# mc_board_with_leds.net
KiCad netlist of a schematic drawn in EAGLE
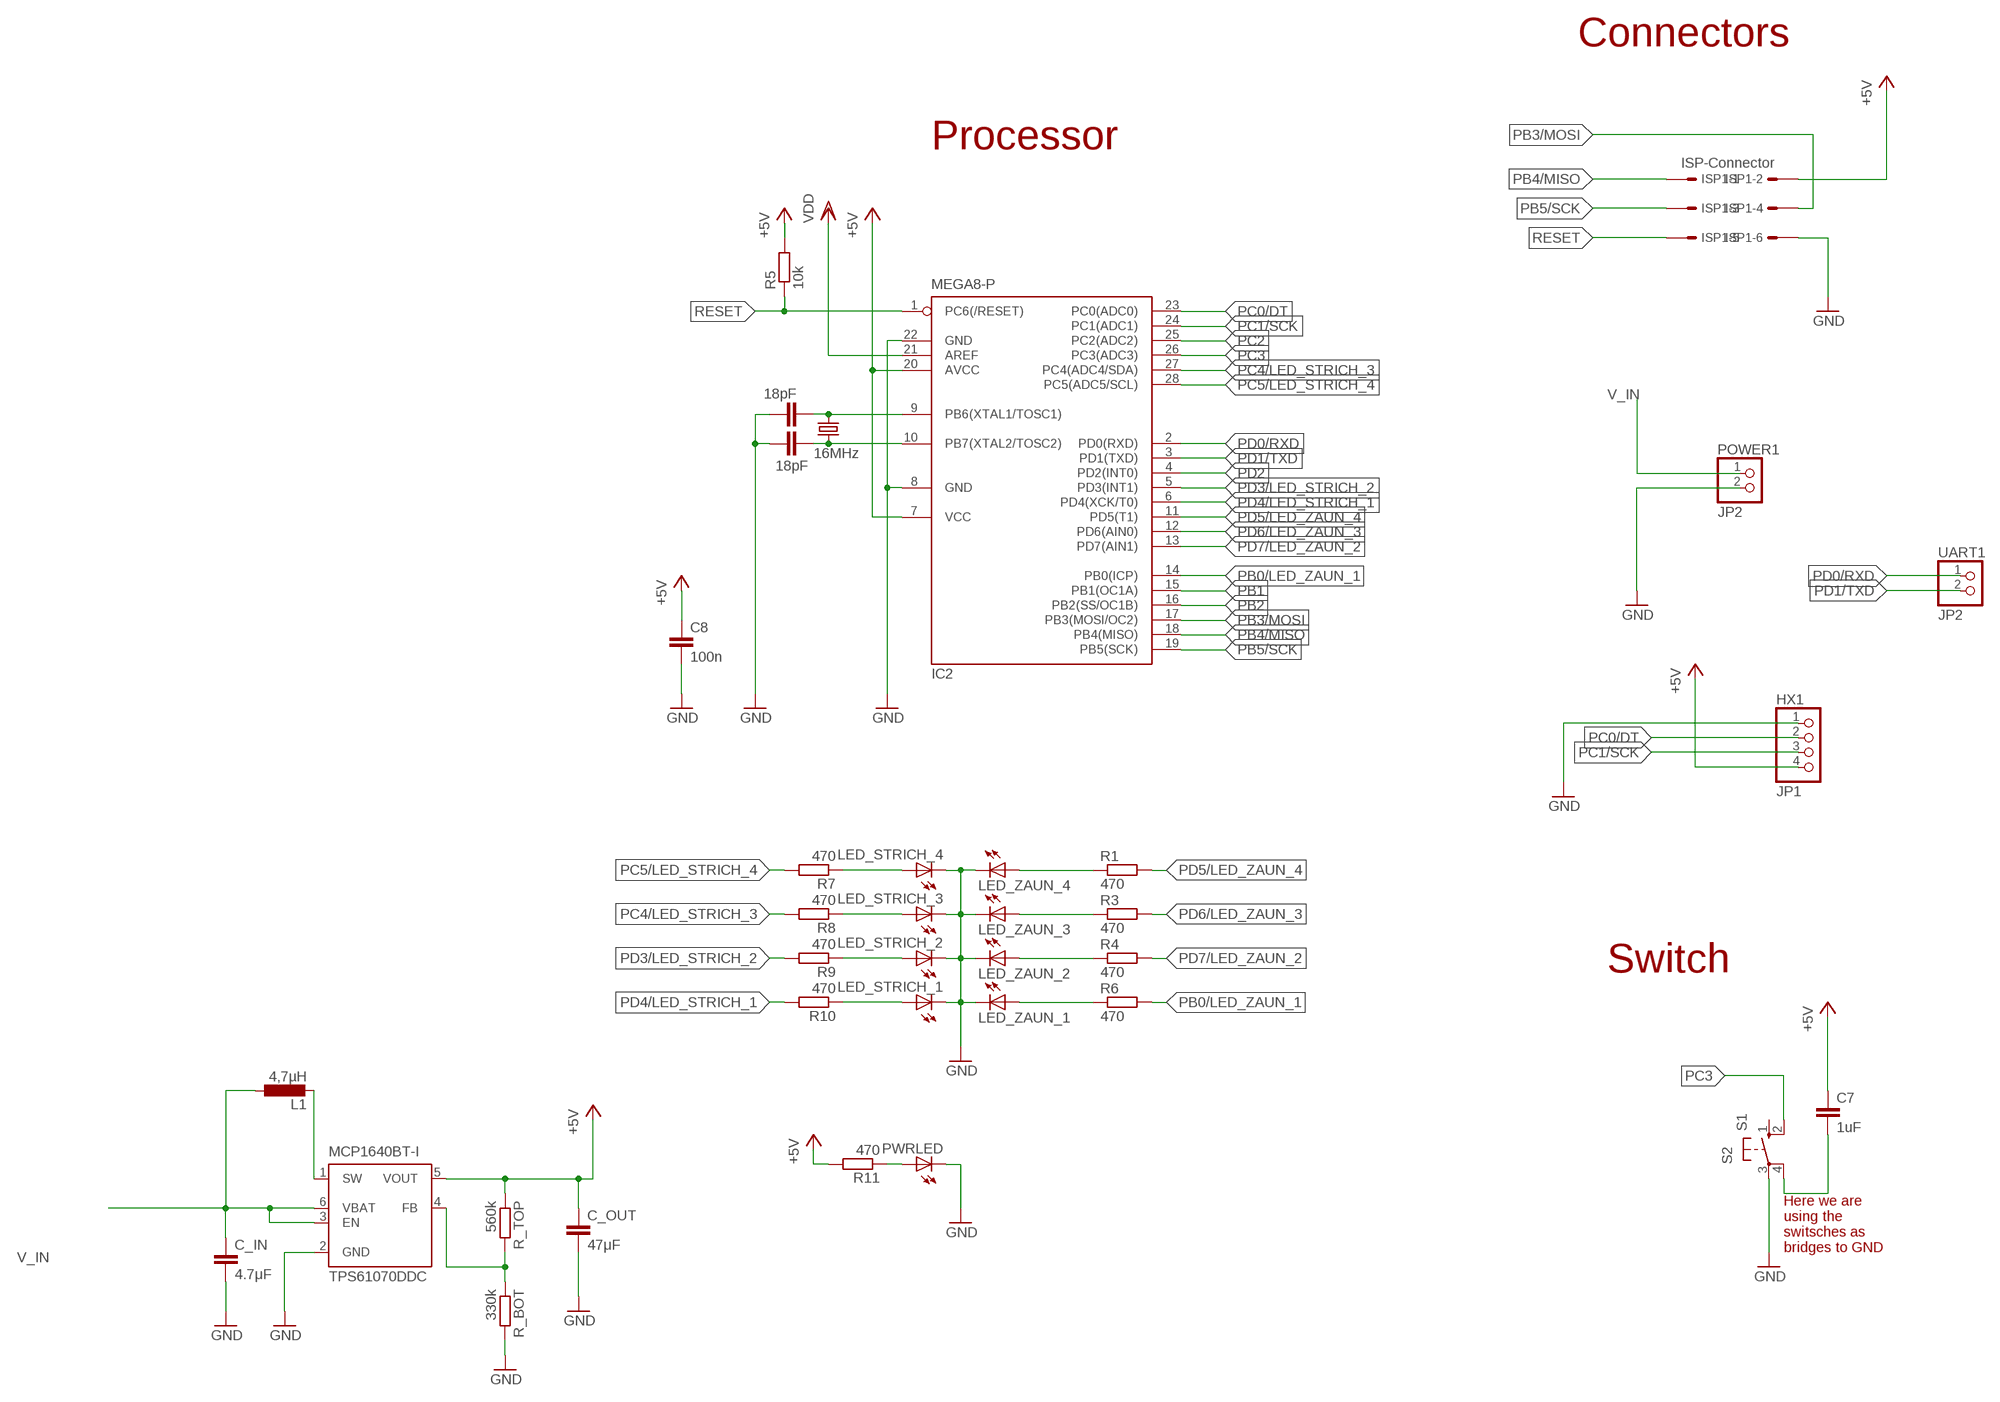
[diagram p0: schematic, sheet 1]

(export (version "E")
  (design (tool "Eeschema 10.0.6"))
  (components
    (comp (ref "C5")
      (value "18pF")
      (footprint "eagle-import:C0805K")
      (libsource (lib "eagle-import") (part "resistor_C-EUC0805K"))
    )
    (comp (ref "C6")
      (value "18pF")
      (footprint "eagle-import:C0805K")
      (libsource (lib "eagle-import") (part "resistor_C-EUC0805K"))
    )
    (comp (ref "C7")
      (value "1uF")
      (footprint "eagle-import:C0805")
      (libsource (lib "eagle-import") (part "C-EUC0805"))
    )
    (comp (ref "C8")
      (value "100n")
      (footprint "eagle-import:C0805")
      (libsource (lib "eagle-import") (part "C-EUC0805"))
    )
    (comp (ref "C_IN")
      (value "4.7μF")
      (footprint "eagle-import:C0805")
      (libsource (lib "eagle-import") (part "C-EUC0805"))
    )
    (comp (ref "C_OUT")
      (value "47μF")
      (footprint "eagle-import:C0805")
      (libsource (lib "eagle-import") (part "C-EUC0805"))
    )
    (comp (ref "HX1")
      (value "JP1")
      (footprint "eagle-import:1X04")
      (libsource (lib "eagle-import") (part "PINHD-1X4"))
    )
    (comp (ref "IC2")
      (value "MEGA8-P")
      (footprint "eagle-import:DIL28-3")
      (libsource (lib "eagle-import") (part "MEGA8-P"))
    )
    (comp (ref "ISP1")
      (value "ISP-Connector")
      (footprint "eagle-import:057-006-1")
      (libsource (lib "eagle-import") (part "057-006-1"))
    )
    (comp (ref "L1")
      (value "4,7µH")
      (footprint "eagle-import:L4532P")
      (libsource (lib "eagle-import") (part "L-EUL4532P"))
    )
    (comp (ref "LED_STRICH_1")
      (value "LED3MM")
      (footprint "eagle-import:LED3MM")
      (libsource (lib "eagle-import") (part "LED3MM"))
    )
    (comp (ref "LED_STRICH_2")
      (value "LED3MM")
      (footprint "eagle-import:LED3MM")
      (libsource (lib "eagle-import") (part "LED3MM"))
    )
    (comp (ref "LED_STRICH_3")
      (value "LED3MM")
      (footprint "eagle-import:LED3MM")
      (libsource (lib "eagle-import") (part "LED3MM"))
    )
    (comp (ref "LED_STRICH_4")
      (value "LED3MM")
      (footprint "eagle-import:LED3MM")
      (libsource (lib "eagle-import") (part "LED3MM"))
    )
    (comp (ref "LED_ZAUN_1")
      (value "LED3MM")
      (footprint "eagle-import:LED3MM")
      (libsource (lib "eagle-import") (part "LED3MM"))
    )
    (comp (ref "LED_ZAUN_2")
      (value "LED3MM")
      (footprint "eagle-import:LED3MM")
      (libsource (lib "eagle-import") (part "LED3MM"))
    )
    (comp (ref "LED_ZAUN_3")
      (value "LED3MM")
      (footprint "eagle-import:LED3MM")
      (libsource (lib "eagle-import") (part "LED3MM"))
    )
    (comp (ref "LED_ZAUN_4")
      (value "LED3MM")
      (footprint "eagle-import:LED3MM")
      (libsource (lib "eagle-import") (part "LED3MM"))
    )
    (comp (ref "MCP1640BT-I")
      (value "TPS61070DDC")
      (footprint "eagle-import:TSOT23-6_DDC")
      (fields (field (name "MPN") "TPS61070DDCR"))
      (libsource (lib "eagle-import") (part "TPS6107DDC0"))
    )
    (comp (ref "POWER1")
      (value "JP2")
      (footprint "eagle-import:1X02")
      (libsource (lib "eagle-import") (part "PINHD-1X2"))
    )
    (comp (ref "PWRLED")
      (value "LED3MM")
      (footprint "eagle-import:LED3MM")
      (libsource (lib "eagle-import") (part "LED3MM"))
    )
    (comp (ref "Q2")
      (value "16MHz")
      (footprint "eagle-import:HC49_S")
      (libsource (lib "eagle-import") (part "CRYSTALHC49S"))
    )
    (comp (ref "R1")
      (value "470")
      (footprint "eagle-import:R0805")
      (libsource (lib "eagle-import") (part "resistor_R-EU_R0805"))
    )
    (comp (ref "R3")
      (value "470")
      (footprint "eagle-import:R0805")
      (libsource (lib "eagle-import") (part "resistor_R-EU_R0805"))
    )
    (comp (ref "R4")
      (value "470")
      (footprint "eagle-import:R0805")
      (libsource (lib "eagle-import") (part "resistor_R-EU_R0805"))
    )
    (comp (ref "R5")
      (value "10k")
      (footprint "eagle-import:R1206")
      (libsource (lib "eagle-import") (part "R-EU_R1206"))
    )
    (comp (ref "R6")
      (value "470")
      (footprint "eagle-import:R0805")
      (libsource (lib "eagle-import") (part "resistor_R-EU_R0805"))
    )
    (comp (ref "R7")
      (value "470")
      (footprint "eagle-import:R0805")
      (libsource (lib "eagle-import") (part "resistor_R-EU_R0805"))
    )
    (comp (ref "R8")
      (value "470")
      (footprint "eagle-import:R0805")
      (libsource (lib "eagle-import") (part "resistor_R-EU_R0805"))
    )
    (comp (ref "R9")
      (value "470")
      (footprint "eagle-import:R0805")
      (libsource (lib "eagle-import") (part "resistor_R-EU_R0805"))
    )
    (comp (ref "R10")
      (value "470")
      (footprint "eagle-import:R0805")
      (libsource (lib "eagle-import") (part "resistor_R-EU_R0805"))
    )
    (comp (ref "R11")
      (value "470")
      (footprint "eagle-import:R0805")
      (libsource (lib "eagle-import") (part "resistor_R-EU_R0805"))
    )
    (comp (ref "R_BOT")
      (value "330k")
      (footprint "eagle-import:R0805")
      (libsource (lib "eagle-import") (part "resistor_R-EU_R0805"))
    )
    (comp (ref "R_TOP")
      (value "560k")
      (footprint "eagle-import:R0805")
      (libsource (lib "eagle-import") (part "resistor_R-EU_R0805"))
    )
    (comp (ref "S2")
      (value "S1")
      (footprint "eagle-import:B3F-10XX")
      (fields (field (name "MPN") "B3F-1000"))
      (libsource (lib "eagle-import") (part "10-XX"))
    )
    (comp (ref "UART1")
      (value "JP2")
      (footprint "eagle-import:1X02")
      (libsource (lib "eagle-import") (part "PINHD-1X2"))
    )
  )
  (nets
    (net (code "1") (name "+5V") (class "Default")
      (node (ref "C7") (pin "1") (pinfunction "1_1") (pintype "passive"))
      (node (ref "C8") (pin "1") (pinfunction "1_1") (pintype "passive"))
      (node (ref "C_OUT") (pin "1") (pinfunction "1_1") (pintype "passive"))
      (node (ref "HX1") (pin "4") (pinfunction "4_4") (pintype "passive"))
      (node (ref "IC2") (pin "20") (pinfunction "AVCC_20") (pintype "power_in"))
      (node (ref "IC2") (pin "7") (pinfunction "VCC_7") (pintype "power_in"))
      (node (ref "ISP1") (pin "2") (pinfunction "S_2") (pintype "passive"))
      (node (ref "MCP1640BT-I") (pin "5") (pinfunction "VOUT_5") (pintype "passive"))
      (node (ref "R11") (pin "2") (pinfunction "2_2") (pintype "passive"))
      (node (ref "R5") (pin "2") (pinfunction "2_2") (pintype "passive"))
      (node (ref "R_TOP") (pin "1") (pinfunction "1_1") (pintype "passive"))
    )
    (net (code "2") (name "/V_IN") (class "Default")
      (node (ref "C_IN") (pin "1") (pinfunction "1_1") (pintype "passive"))
      (node (ref "L1") (pin "1") (pinfunction "1_1") (pintype "passive"))
      (node (ref "MCP1640BT-I") (pin "3") (pinfunction "EN_3") (pintype "input"))
      (node (ref "MCP1640BT-I") (pin "6") (pinfunction "VBAT_6") (pintype "input"))
      (node (ref "POWER1") (pin "1") (pinfunction "1_1") (pintype "passive"))
    )
    (net (code "3") (name "GND") (class "Default")
      (node (ref "C5") (pin "2") (pinfunction "2_2") (pintype "passive"))
      (node (ref "C6") (pin "2") (pinfunction "2_2") (pintype "passive"))
      (node (ref "C8") (pin "2") (pinfunction "2_2") (pintype "passive"))
      (node (ref "C_IN") (pin "2") (pinfunction "2_2") (pintype "passive"))
      (node (ref "C_OUT") (pin "2") (pinfunction "2_2") (pintype "passive"))
      (node (ref "HX1") (pin "1") (pinfunction "1_1") (pintype "passive"))
      (node (ref "IC2") (pin "22") (pinfunction "GND_22") (pintype "power_in"))
      (node (ref "IC2") (pin "8") (pinfunction "GND_8") (pintype "power_in"))
      (node (ref "ISP1") (pin "6") (pinfunction "S_6") (pintype "passive"))
      (node (ref "LED_STRICH_1") (pin "K") (pinfunction "C_K") (pintype "passive"))
      (node (ref "LED_STRICH_2") (pin "K") (pinfunction "C_K") (pintype "passive"))
      (node (ref "LED_STRICH_3") (pin "K") (pinfunction "C_K") (pintype "passive"))
      (node (ref "LED_STRICH_4") (pin "K") (pinfunction "C_K") (pintype "passive"))
      (node (ref "LED_ZAUN_1") (pin "K") (pinfunction "C_K") (pintype "passive"))
      (node (ref "LED_ZAUN_2") (pin "K") (pinfunction "C_K") (pintype "passive"))
      (node (ref "LED_ZAUN_3") (pin "K") (pinfunction "C_K") (pintype "passive"))
      (node (ref "LED_ZAUN_4") (pin "K") (pinfunction "C_K") (pintype "passive"))
      (node (ref "MCP1640BT-I") (pin "2") (pinfunction "GND_2") (pintype "power_in"))
      (node (ref "POWER1") (pin "2") (pinfunction "2_2") (pintype "passive"))
      (node (ref "PWRLED") (pin "K") (pinfunction "C_K") (pintype "passive"))
      (node (ref "R_BOT") (pin "2") (pinfunction "2_2") (pintype "passive"))
      (node (ref "S2") (pin "3") (pinfunction "P_3") (pintype "passive"))
    )
    (net (code "4") (name "Net-(IC2-PB6(XTAL1{slash}TOSC1))") (class "Default")
      (node (ref "C6") (pin "1") (pinfunction "1_1") (pintype "passive"))
      (node (ref "IC2") (pin "9") (pinfunction "PB6(XTAL1/TOSC1)_9") (pintype "bidirectional"))
      (node (ref "Q2") (pin "1") (pinfunction "1_1") (pintype "passive"))
    )
    (net (code "5") (name "Net-(IC2-PB7(XTAL2{slash}TOSC2))") (class "Default")
      (node (ref "C5") (pin "1") (pinfunction "1_1") (pintype "passive"))
      (node (ref "IC2") (pin "10") (pinfunction "PB7(XTAL2/TOSC2)_10") (pintype "bidirectional"))
      (node (ref "Q2") (pin "2") (pinfunction "2_2") (pintype "passive"))
    )
    (net (code "6") (name "Net-(LED_STRICH_1-PadA)") (class "Default")
      (node (ref "LED_STRICH_1") (pin "A") (pinfunction "A_A") (pintype "passive"))
      (node (ref "R10") (pin "1") (pinfunction "1_1") (pintype "passive"))
    )
    (net (code "7") (name "Net-(LED_STRICH_2-PadA)") (class "Default")
      (node (ref "LED_STRICH_2") (pin "A") (pinfunction "A_A") (pintype "passive"))
      (node (ref "R9") (pin "1") (pinfunction "1_1") (pintype "passive"))
    )
    (net (code "8") (name "Net-(LED_STRICH_3-PadA)") (class "Default")
      (node (ref "LED_STRICH_3") (pin "A") (pinfunction "A_A") (pintype "passive"))
      (node (ref "R8") (pin "1") (pinfunction "1_1") (pintype "passive"))
    )
    (net (code "9") (name "Net-(LED_STRICH_4-PadA)") (class "Default")
      (node (ref "LED_STRICH_4") (pin "A") (pinfunction "A_A") (pintype "passive"))
      (node (ref "R7") (pin "1") (pinfunction "1_1") (pintype "passive"))
    )
    (net (code "10") (name "Net-(LED_ZAUN_1-PadA)") (class "Default")
      (node (ref "LED_ZAUN_1") (pin "A") (pinfunction "A_A") (pintype "passive"))
      (node (ref "R6") (pin "1") (pinfunction "1_1") (pintype "passive"))
    )
    (net (code "11") (name "Net-(LED_ZAUN_2-PadA)") (class "Default")
      (node (ref "LED_ZAUN_2") (pin "A") (pinfunction "A_A") (pintype "passive"))
      (node (ref "R4") (pin "1") (pinfunction "1_1") (pintype "passive"))
    )
    (net (code "12") (name "Net-(LED_ZAUN_3-PadA)") (class "Default")
      (node (ref "LED_ZAUN_3") (pin "A") (pinfunction "A_A") (pintype "passive"))
      (node (ref "R3") (pin "1") (pinfunction "1_1") (pintype "passive"))
    )
    (net (code "13") (name "Net-(LED_ZAUN_4-PadA)") (class "Default")
      (node (ref "LED_ZAUN_4") (pin "A") (pinfunction "A_A") (pintype "passive"))
      (node (ref "R1") (pin "1") (pinfunction "1_1") (pintype "passive"))
    )
    (net (code "14") (name "Net-(MCP1640BT-I-FB)") (class "Default")
      (node (ref "MCP1640BT-I") (pin "4") (pinfunction "FB_4") (pintype "input"))
      (node (ref "R_BOT") (pin "1") (pinfunction "1_1") (pintype "passive"))
      (node (ref "R_TOP") (pin "2") (pinfunction "2_2") (pintype "passive"))
    )
    (net (code "15") (name "Net-(MCP1640BT-I-SW)") (class "Default")
      (node (ref "L1") (pin "2") (pinfunction "2_2") (pintype "passive"))
      (node (ref "MCP1640BT-I") (pin "1") (pinfunction "SW_1") (pintype "input"))
    )
    (net (code "16") (name "Net-(PWRLED-PadA)") (class "Default")
      (node (ref "PWRLED") (pin "A") (pinfunction "A_A") (pintype "passive"))
      (node (ref "R11") (pin "1") (pinfunction "1_1") (pintype "passive"))
    )
    (net (code "17") (name "Net-(S2-P1)") (class "Default")
      (node (ref "C7") (pin "2") (pinfunction "2_2") (pintype "passive"))
      (node (ref "S2") (pin "4") (pinfunction "P1_4") (pintype "passive"))
    )
    (net (code "18") (name "PB0{slash}LED_ZAUN_1") (class "Default")
      (node (ref "IC2") (pin "14") (pinfunction "PB0(ICP)_14") (pintype "bidirectional"))
      (node (ref "R6") (pin "2") (pinfunction "2_2") (pintype "passive"))
    )
    (net (code "19") (name "PB1") (class "Default")
      (node (ref "IC2") (pin "15") (pinfunction "PB1(OC1A)_15") (pintype "bidirectional"))
    )
    (net (code "20") (name "PB2") (class "Default")
      (node (ref "IC2") (pin "16") (pinfunction "PB2(SS/OC1B)_16") (pintype "bidirectional"))
    )
    (net (code "21") (name "PB3{slash}MOSI") (class "Default")
      (node (ref "IC2") (pin "17") (pinfunction "PB3(MOSI/OC2)_17") (pintype "bidirectional"))
      (node (ref "ISP1") (pin "4") (pinfunction "S_4") (pintype "passive"))
    )
    (net (code "22") (name "PB4{slash}MISO") (class "Default")
      (node (ref "IC2") (pin "18") (pinfunction "PB4(MISO)_18") (pintype "bidirectional"))
      (node (ref "ISP1") (pin "1") (pinfunction "S_1") (pintype "passive"))
    )
    (net (code "23") (name "PB5{slash}SCK") (class "Default")
      (node (ref "IC2") (pin "19") (pinfunction "PB5(SCK)_19") (pintype "bidirectional"))
      (node (ref "ISP1") (pin "3") (pinfunction "S_3") (pintype "passive"))
    )
    (net (code "24") (name "PC0{slash}DT") (class "Default")
      (node (ref "HX1") (pin "2") (pinfunction "2_2") (pintype "passive"))
      (node (ref "IC2") (pin "23") (pinfunction "PC0(ADC0)_23") (pintype "bidirectional"))
    )
    (net (code "25") (name "PC1{slash}SCK") (class "Default")
      (node (ref "HX1") (pin "3") (pinfunction "3_3") (pintype "passive"))
      (node (ref "IC2") (pin "24") (pinfunction "PC1(ADC1)_24") (pintype "bidirectional"))
    )
    (net (code "26") (name "PC2") (class "Default")
      (node (ref "IC2") (pin "25") (pinfunction "PC2(ADC2)_25") (pintype "bidirectional"))
    )
    (net (code "27") (name "PC3") (class "Default")
      (node (ref "IC2") (pin "26") (pinfunction "PC3(ADC3)_26") (pintype "bidirectional"))
      (node (ref "S2") (pin "2") (pinfunction "S1_2") (pintype "passive"))
    )
    (net (code "28") (name "PC4{slash}LED_STRICH_3") (class "Default")
      (node (ref "IC2") (pin "27") (pinfunction "PC4(ADC4/SDA)_27") (pintype "bidirectional"))
      (node (ref "R8") (pin "2") (pinfunction "2_2") (pintype "passive"))
    )
    (net (code "29") (name "PC5{slash}LED_STRICH_4") (class "Default")
      (node (ref "IC2") (pin "28") (pinfunction "PC5(ADC5/SCL)_28") (pintype "bidirectional"))
      (node (ref "R7") (pin "2") (pinfunction "2_2") (pintype "passive"))
    )
    (net (code "30") (name "PD0{slash}RXD") (class "Default")
      (node (ref "IC2") (pin "2") (pinfunction "PD0(RXD)_2") (pintype "bidirectional"))
      (node (ref "UART1") (pin "1") (pinfunction "1_1") (pintype "passive"))
    )
    (net (code "31") (name "PD1{slash}TXD") (class "Default")
      (node (ref "IC2") (pin "3") (pinfunction "PD1(TXD)_3") (pintype "bidirectional"))
      (node (ref "UART1") (pin "2") (pinfunction "2_2") (pintype "passive"))
    )
    (net (code "32") (name "PD2") (class "Default")
      (node (ref "IC2") (pin "4") (pinfunction "PD2(INT0)_4") (pintype "bidirectional"))
    )
    (net (code "33") (name "PD3{slash}LED_STRICH_2") (class "Default")
      (node (ref "IC2") (pin "5") (pinfunction "PD3(INT1)_5") (pintype "bidirectional"))
      (node (ref "R9") (pin "2") (pinfunction "2_2") (pintype "passive"))
    )
    (net (code "34") (name "PD4{slash}LED_STRICH_1") (class "Default")
      (node (ref "IC2") (pin "6") (pinfunction "PD4(XCK/T0)_6") (pintype "bidirectional"))
      (node (ref "R10") (pin "2") (pinfunction "2_2") (pintype "passive"))
    )
    (net (code "35") (name "PD5{slash}LED_ZAUN_4") (class "Default")
      (node (ref "IC2") (pin "11") (pinfunction "PD5(T1)_11") (pintype "bidirectional"))
      (node (ref "R1") (pin "2") (pinfunction "2_2") (pintype "passive"))
    )
    (net (code "36") (name "PD6{slash}LED_ZAUN_3") (class "Default")
      (node (ref "IC2") (pin "12") (pinfunction "PD6(AIN0)_12") (pintype "bidirectional"))
      (node (ref "R3") (pin "2") (pinfunction "2_2") (pintype "passive"))
    )
    (net (code "37") (name "PD7{slash}LED_ZAUN_2") (class "Default")
      (node (ref "IC2") (pin "13") (pinfunction "PD7(AIN1)_13") (pintype "bidirectional"))
      (node (ref "R4") (pin "2") (pinfunction "2_2") (pintype "passive"))
    )
    (net (code "38") (name "RESET") (class "Default")
      (node (ref "IC2") (pin "1") (pinfunction "PC6(/RESET)_1") (pintype "bidirectional"))
      (node (ref "ISP1") (pin "5") (pinfunction "S_5") (pintype "passive"))
      (node (ref "R5") (pin "1") (pinfunction "1_1") (pintype "passive"))
    )
    (net (code "39") (name "VDD") (class "Default")
      (node (ref "IC2") (pin "21") (pinfunction "AREF_21") (pintype "passive"))
    )
    (net (code "40") (name "unconnected-(S2-S-Pad1)") (class "Default")
      (node (ref "S2") (pin "1") (pinfunction "S_1") (pintype "passive"))
    )
  )
)
